# CoreBoard.net
KiCad netlist of a schematic drawn in Altium Designer
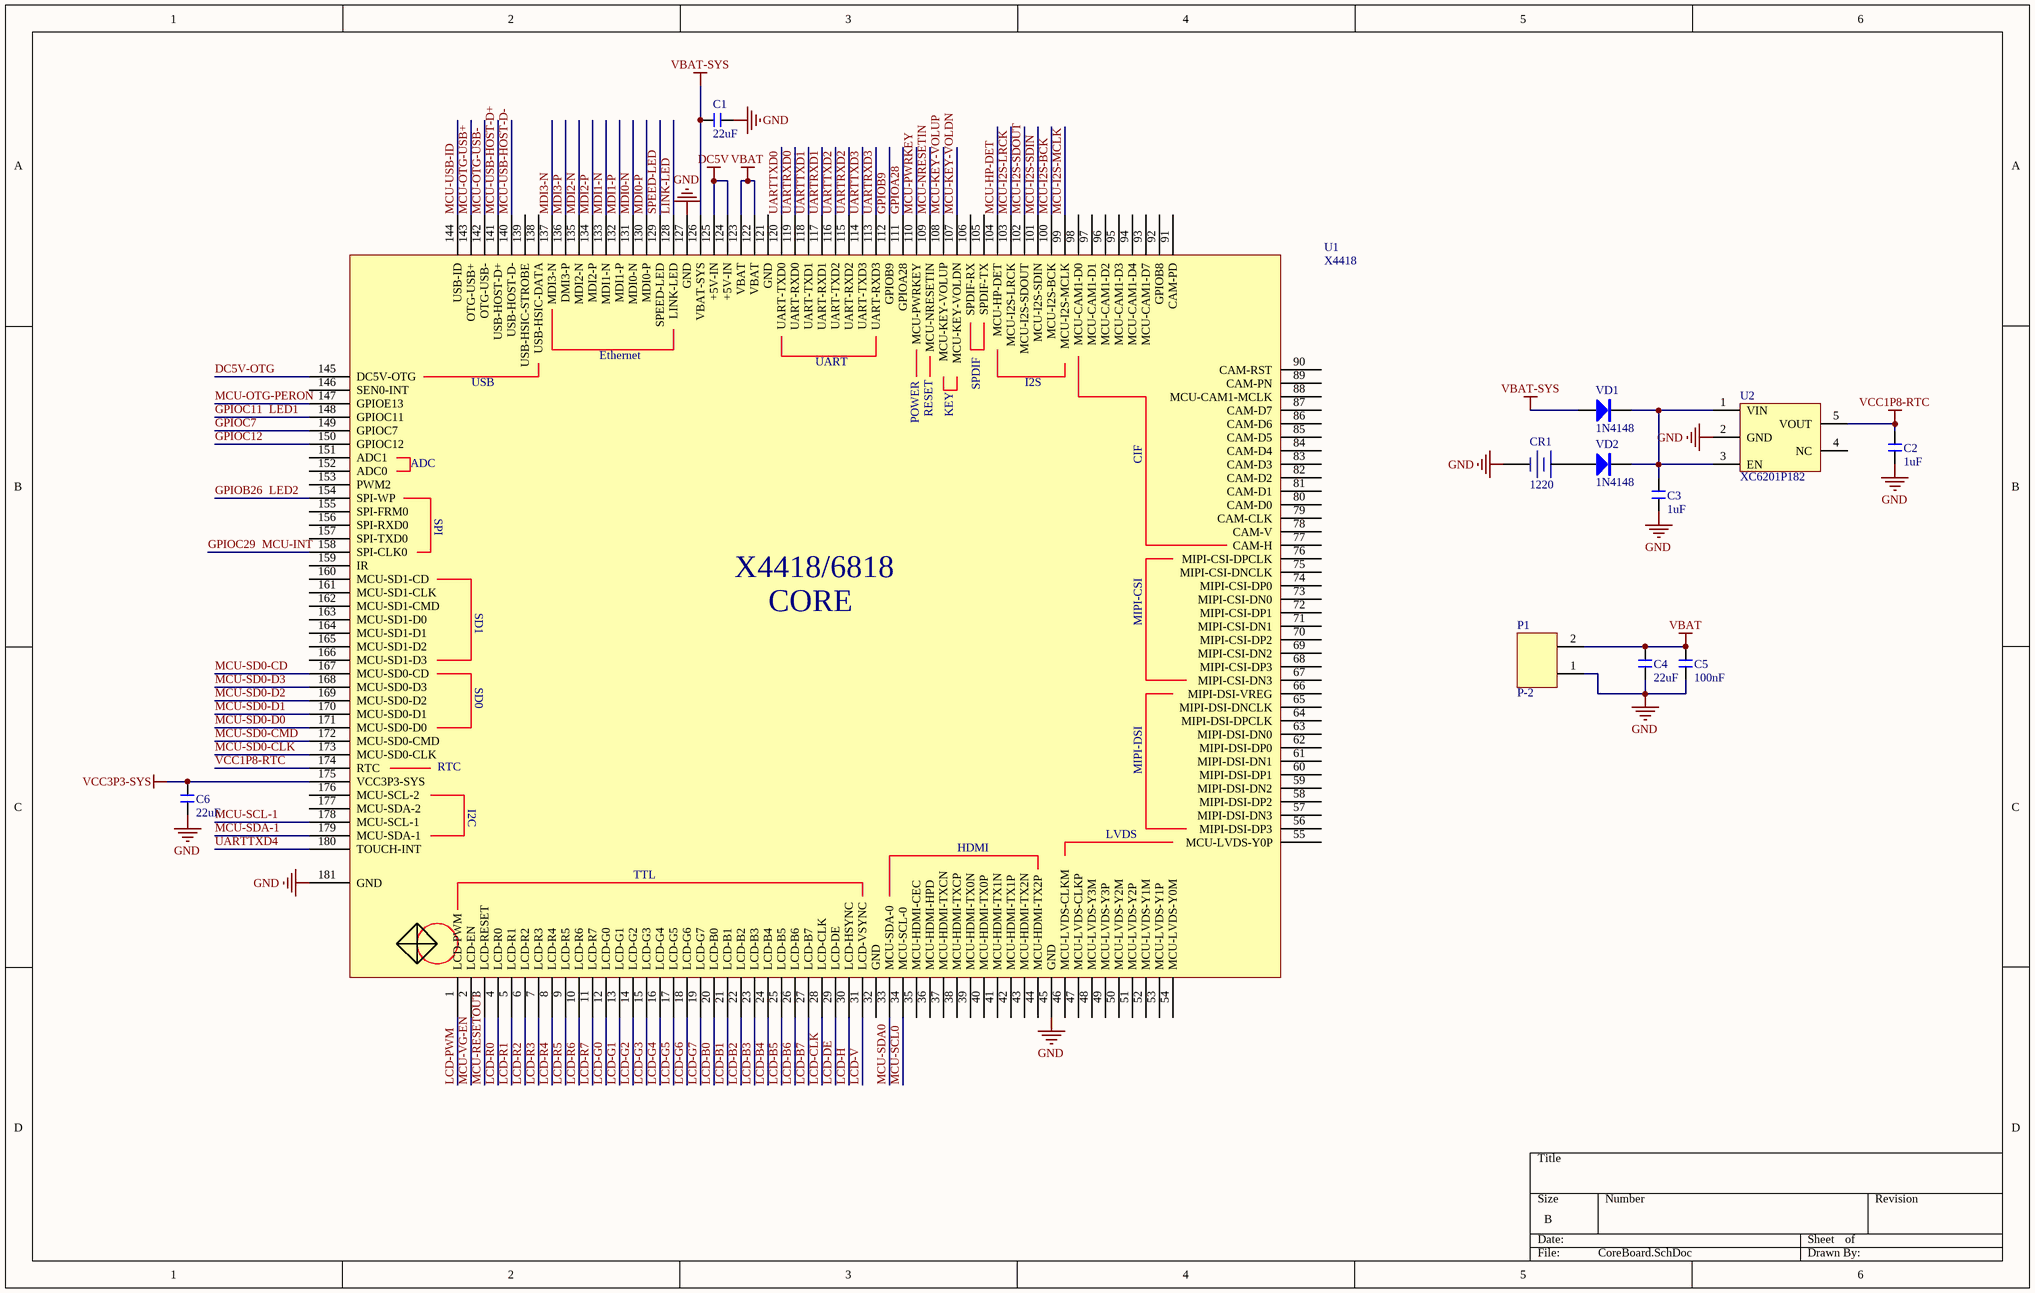
[diagram p0: CoreBoard.SchDoc]

(export (version "E")
  (design (tool "Eeschema 10.0.6"))
  (components
    (comp (ref "C1")
      (value "22uF")
      (footprint "C 0805")
      (description "无极性贴片电容")
      (fields (field (name "版权归属") "源创客"))
      (libsource (lib "ZZF_Library") (part "C 22uF"))
    )
    (comp (ref "C2")
      (value "1uF")
      (footprint "C 0402")
      (description "无极性贴片电容")
      (fields (field (name "版权归属") "源创客"))
      (libsource (lib "ZZF_Library") (part "C 1uF"))
    )
    (comp (ref "C3")
      (value "1uF")
      (footprint "C 0402")
      (description "无极性贴片电容")
      (fields (field (name "版权归属") "源创客"))
      (libsource (lib "ZZF_Library") (part "C 1uF"))
    )
    (comp (ref "C4")
      (value "22uF")
      (footprint "C 0805")
      (description "无极性贴片电容")
      (fields (field (name "版权归属") "源创客"))
      (libsource (lib "ZZF_Library") (part "C 22uF"))
    )
    (comp (ref "C5")
      (value "100nF")
      (footprint "C 0402")
      (description "无极性贴片电容")
      (fields (field (name "版权归属") "源创客"))
      (libsource (lib "ZZF_Library") (part "C 100nF"))
    )
    (comp (ref "C6")
      (value "22uF")
      (footprint "C 0805")
      (description "无极性贴片电容")
      (fields (field (name "版权归属") "源创客"))
      (libsource (lib "ZZF_Library") (part "C 22uF"))
    )
    (comp (ref "CR1")
      (value "1220")
      (footprint "BATTERY CR1220_A")
      (description "微型电池")
      (fields (field (name "版权归属") "源创客"))
      (libsource (lib "ZZF_Library") (part "BATTERY-CR-3V"))
    )
    (comp (ref "P1")
      (value "P-2")
      (footprint "P 2EDG3.5-2H")
      (description "2脚接插件")
      (libsource (lib "ZZF_Library") (part "P-2"))
    )
    (comp (ref "U1")
      (value "X4418")
      (footprint "CORE 4418/6818")
      (description "安卓核心板")
      (libsource (lib "ZZF_Library") (part "CORE X4418/6818"))
    )
    (comp (ref "U2")
      (value "XC6201P182")
      (footprint "SOT23-5M")
      (description "1.8V线性稳压芯片")
      (libsource (lib "ZZF_Library") (part "XC6201P182"))
    )
    (comp (ref "VD1")
      (value "1N4148")
      (footprint "D SOD-323")
      (description "高速开关二极管")
      (fields (field (name "版权归属") "源创客"))
      (libsource (lib "ZZF_Library") (part "1N4148"))
    )
    (comp (ref "VD2")
      (value "1N4148")
      (footprint "D SOD-323")
      (description "高速开关二极管")
      (fields (field (name "版权归属") "源创客"))
      (libsource (lib "ZZF_Library") (part "1N4148"))
    )
  )
  (nets
    (net (code "1") (name "/DC5V-OTG") (class "Default")
      (node (ref "U1") (pin "145") (pinfunction "DC5V-OTG_145") (pintype "passive"))
    )
    (net (code "2") (name "/GPIOA28") (class "Default")
      (node (ref "U1") (pin "111") (pinfunction "GPIOA28_111") (pintype "passive"))
    )
    (net (code "3") (name "/GPIOB9") (class "Default")
      (node (ref "U1") (pin "112") (pinfunction "GPIOB9_112") (pintype "passive"))
    )
    (net (code "4") (name "/GPIOB26") (class "Default")
      (node (ref "U1") (pin "154") (pinfunction "SPI-WP_154") (pintype "passive"))
    )
    (net (code "5") (name "/GPIOC7") (class "Default")
      (node (ref "U1") (pin "149") (pinfunction "GPIOC7_149") (pintype "passive"))
    )
    (net (code "6") (name "/GPIOC11") (class "Default")
      (node (ref "U1") (pin "148") (pinfunction "GPIOC11_148") (pintype "passive"))
    )
    (net (code "7") (name "/GPIOC12") (class "Default")
      (node (ref "U1") (pin "150") (pinfunction "GPIOC12_150") (pintype "passive"))
    )
    (net (code "8") (name "/GPIOC29") (class "Default")
      (node (ref "U1") (pin "158") (pinfunction "SPI-CLK0_158") (pintype "passive"))
    )
    (net (code "9") (name "/LCD-B0") (class "Default")
      (node (ref "U1") (pin "20") (pinfunction "LCD-B0_20") (pintype "passive"))
    )
    (net (code "10") (name "/LCD-B1") (class "Default")
      (node (ref "U1") (pin "21") (pinfunction "LCD-B1_21") (pintype "passive"))
    )
    (net (code "11") (name "/LCD-B2") (class "Default")
      (node (ref "U1") (pin "22") (pinfunction "LCD-B2_22") (pintype "passive"))
    )
    (net (code "12") (name "/LCD-B3") (class "Default")
      (node (ref "U1") (pin "23") (pinfunction "LCD-B3_23") (pintype "passive"))
    )
    (net (code "13") (name "/LCD-B4") (class "Default")
      (node (ref "U1") (pin "24") (pinfunction "LCD-B4_24") (pintype "passive"))
    )
    (net (code "14") (name "/LCD-B5") (class "Default")
      (node (ref "U1") (pin "25") (pinfunction "LCD-B5_25") (pintype "passive"))
    )
    (net (code "15") (name "/LCD-B6") (class "Default")
      (node (ref "U1") (pin "26") (pinfunction "LCD-B6_26") (pintype "passive"))
    )
    (net (code "16") (name "/LCD-B7") (class "Default")
      (node (ref "U1") (pin "27") (pinfunction "LCD-B7_27") (pintype "passive"))
    )
    (net (code "17") (name "/LCD-CLK") (class "Default")
      (node (ref "U1") (pin "28") (pinfunction "LCD-CLK_28") (pintype "passive"))
    )
    (net (code "18") (name "/LCD-DE") (class "Default")
      (node (ref "U1") (pin "29") (pinfunction "LCD-DE_29") (pintype "passive"))
    )
    (net (code "19") (name "/LCD-G0") (class "Default")
      (node (ref "U1") (pin "12") (pinfunction "LCD-G0_12") (pintype "passive"))
    )
    (net (code "20") (name "/LCD-G1") (class "Default")
      (node (ref "U1") (pin "13") (pinfunction "LCD-G1_13") (pintype "passive"))
    )
    (net (code "21") (name "/LCD-G2") (class "Default")
      (node (ref "U1") (pin "14") (pinfunction "LCD-G2_14") (pintype "passive"))
    )
    (net (code "22") (name "/LCD-G3") (class "Default")
      (node (ref "U1") (pin "15") (pinfunction "LCD-G3_15") (pintype "passive"))
    )
    (net (code "23") (name "/LCD-G4") (class "Default")
      (node (ref "U1") (pin "16") (pinfunction "LCD-G4_16") (pintype "passive"))
    )
    (net (code "24") (name "/LCD-G5") (class "Default")
      (node (ref "U1") (pin "17") (pinfunction "LCD-G5_17") (pintype "passive"))
    )
    (net (code "25") (name "/LCD-G6") (class "Default")
      (node (ref "U1") (pin "18") (pinfunction "LCD-G6_18") (pintype "passive"))
    )
    (net (code "26") (name "/LCD-G7") (class "Default")
      (node (ref "U1") (pin "19") (pinfunction "LCD-G7_19") (pintype "passive"))
    )
    (net (code "27") (name "/LCD-H") (class "Default")
      (node (ref "U1") (pin "30") (pinfunction "LCD-HSYNC_30") (pintype "passive"))
    )
    (net (code "28") (name "/LCD-PWM") (class "Default")
      (node (ref "U1") (pin "1") (pinfunction "LCD-PWM_1") (pintype "passive"))
    )
    (net (code "29") (name "/LCD-R0") (class "Default")
      (node (ref "U1") (pin "4") (pinfunction "LCD-R0_4") (pintype "passive"))
    )
    (net (code "30") (name "/LCD-R1") (class "Default")
      (node (ref "U1") (pin "5") (pinfunction "LCD-R1_5") (pintype "passive"))
    )
    (net (code "31") (name "/LCD-R2") (class "Default")
      (node (ref "U1") (pin "6") (pinfunction "LCD-R2_6") (pintype "passive"))
    )
    (net (code "32") (name "/LCD-R3") (class "Default")
      (node (ref "U1") (pin "7") (pinfunction "LCD-R3_7") (pintype "passive"))
    )
    (net (code "33") (name "/LCD-R4") (class "Default")
      (node (ref "U1") (pin "8") (pinfunction "LCD-R4_8") (pintype "passive"))
    )
    (net (code "34") (name "/LCD-R5") (class "Default")
      (node (ref "U1") (pin "9") (pinfunction "LCD-R5_9") (pintype "passive"))
    )
    (net (code "35") (name "/LCD-R6") (class "Default")
      (node (ref "U1") (pin "10") (pinfunction "LCD-R6_10") (pintype "passive"))
    )
    (net (code "36") (name "/LCD-R7") (class "Default")
      (node (ref "U1") (pin "11") (pinfunction "LCD-R7_11") (pintype "passive"))
    )
    (net (code "37") (name "/LCD-V") (class "Default")
      (node (ref "U1") (pin "31") (pinfunction "LCD-VSYNC_31") (pintype "passive"))
    )
    (net (code "38") (name "/LINK-LED") (class "Default")
      (node (ref "U1") (pin "128") (pinfunction "LINK-LED_128") (pintype "passive"))
    )
    (net (code "39") (name "/MCU-HP-DET") (class "Default")
      (node (ref "U1") (pin "104") (pinfunction "MCU-HP-DET_104") (pintype "passive"))
    )
    (net (code "40") (name "/MCU-I2S-BCK") (class "Default")
      (node (ref "U1") (pin "100") (pinfunction "MCU-I2S-BCK_100") (pintype "passive"))
    )
    (net (code "41") (name "/MCU-I2S-LRCK") (class "Default")
      (node (ref "U1") (pin "103") (pinfunction "MCU-I2S-LRCK_103") (pintype "passive"))
    )
    (net (code "42") (name "/MCU-I2S-MCLK") (class "Default")
      (node (ref "U1") (pin "99") (pinfunction "MCU-I2S-MCLK_99") (pintype "passive"))
    )
    (net (code "43") (name "/MCU-I2S-SDIN") (class "Default")
      (node (ref "U1") (pin "101") (pinfunction "MCU-I2S-SDIN_101") (pintype "passive"))
    )
    (net (code "44") (name "/MCU-I2S-SDOUT") (class "Default")
      (node (ref "U1") (pin "102") (pinfunction "MCU-I2S-SDOUT_102") (pintype "passive"))
    )
    (net (code "45") (name "/MCU-KEY-VOLDN") (class "Default")
      (node (ref "U1") (pin "107") (pinfunction "MCU-KEY-VOLDN_107") (pintype "passive"))
    )
    (net (code "46") (name "/MCU-KEY-VOLUP") (class "Default")
      (node (ref "U1") (pin "108") (pinfunction "MCU-KEY-VOLUP_108") (pintype "passive"))
    )
    (net (code "47") (name "/MCU-NRESETIN") (class "Default")
      (node (ref "U1") (pin "109") (pinfunction "MCU-NRESETIN_109") (pintype "passive"))
    )
    (net (code "48") (name "/MCU-OTG-PERON") (class "Default")
      (node (ref "U1") (pin "147") (pinfunction "GPIOE13_147") (pintype "passive"))
    )
    (net (code "49") (name "/MCU-OTG-USB+") (class "Default")
      (node (ref "U1") (pin "143") (pinfunction "OTG-USB+_143") (pintype "passive"))
    )
    (net (code "50") (name "/MCU-OTG-USB-") (class "Default")
      (node (ref "U1") (pin "142") (pinfunction "OTG-USB-_142") (pintype "passive"))
    )
    (net (code "51") (name "/MCU-PWRKEY") (class "Default")
      (node (ref "U1") (pin "110") (pinfunction "MCU-PWRKEY_110") (pintype "passive"))
    )
    (net (code "52") (name "/MCU-RESETOUT") (class "Default")
      (node (ref "U1") (pin "3") (pinfunction "LCD-RESET_3") (pintype "passive"))
    )
    (net (code "53") (name "/MCU-SCL-1") (class "Default")
      (node (ref "U1") (pin "178") (pinfunction "MCU-SCL-1_178") (pintype "passive"))
    )
    (net (code "54") (name "/MCU-SCL0") (class "Default")
      (node (ref "U1") (pin "34") (pinfunction "MCU-SCL-0_34") (pintype "passive"))
    )
    (net (code "55") (name "/MCU-SD0-CD") (class "Default")
      (node (ref "U1") (pin "167") (pinfunction "MCU-SD0-CD_167") (pintype "passive"))
    )
    (net (code "56") (name "/MCU-SD0-CLK") (class "Default")
      (node (ref "U1") (pin "173") (pinfunction "MCU-SD0-CLK_173") (pintype "passive"))
    )
    (net (code "57") (name "/MCU-SD0-CMD") (class "Default")
      (node (ref "U1") (pin "172") (pinfunction "MCU-SD0-CMD_172") (pintype "passive"))
    )
    (net (code "58") (name "/MCU-SD0-D0") (class "Default")
      (node (ref "U1") (pin "171") (pinfunction "MCU-SD0-D0_171") (pintype "passive"))
    )
    (net (code "59") (name "/MCU-SD0-D1") (class "Default")
      (node (ref "U1") (pin "170") (pinfunction "MCU-SD0-D1_170") (pintype "passive"))
    )
    (net (code "60") (name "/MCU-SD0-D2") (class "Default")
      (node (ref "U1") (pin "169") (pinfunction "MCU-SD0-D2_169") (pintype "passive"))
    )
    (net (code "61") (name "/MCU-SD0-D3") (class "Default")
      (node (ref "U1") (pin "168") (pinfunction "MCU-SD0-D3_168") (pintype "passive"))
    )
    (net (code "62") (name "/MCU-SDA-1") (class "Default")
      (node (ref "U1") (pin "179") (pinfunction "MCU-SDA-1_179") (pintype "passive"))
    )
    (net (code "63") (name "/MCU-SDA0") (class "Default")
      (node (ref "U1") (pin "33") (pinfunction "MCU-SDA-0_33") (pintype "passive"))
    )
    (net (code "64") (name "/MCU-USB-HOST-D+") (class "Default")
      (node (ref "U1") (pin "141") (pinfunction "USB-HOST-D+_141") (pintype "passive"))
    )
    (net (code "65") (name "/MCU-USB-HOST-D-") (class "Default")
      (node (ref "U1") (pin "140") (pinfunction "USB-HOST-D-_140") (pintype "passive"))
    )
    (net (code "66") (name "/MCU-USB-ID") (class "Default")
      (node (ref "U1") (pin "144") (pinfunction "USB-ID_144") (pintype "passive"))
    )
    (net (code "67") (name "/MCU-VG-EN") (class "Default")
      (node (ref "U1") (pin "2") (pinfunction "LCD-EN_2") (pintype "passive"))
    )
    (net (code "68") (name "/MDI0-N") (class "Default")
      (node (ref "U1") (pin "131") (pinfunction "MDI0-N_131") (pintype "passive"))
    )
    (net (code "69") (name "/MDI0-P") (class "Default")
      (node (ref "U1") (pin "130") (pinfunction "MDI0-P_130") (pintype "passive"))
    )
    (net (code "70") (name "/MDI1-N") (class "Default")
      (node (ref "U1") (pin "133") (pinfunction "MDI1-N_133") (pintype "passive"))
    )
    (net (code "71") (name "/MDI1-P") (class "Default")
      (node (ref "U1") (pin "132") (pinfunction "MDI1-P_132") (pintype "passive"))
    )
    (net (code "72") (name "/MDI2-N") (class "Default")
      (node (ref "U1") (pin "135") (pinfunction "MDI2-N_135") (pintype "passive"))
    )
    (net (code "73") (name "/MDI2-P") (class "Default")
      (node (ref "U1") (pin "134") (pinfunction "MDI2-P_134") (pintype "passive"))
    )
    (net (code "74") (name "/MDI3-N") (class "Default")
      (node (ref "U1") (pin "137") (pinfunction "MDI3-N_137") (pintype "passive"))
    )
    (net (code "75") (name "/MDI3-P") (class "Default")
      (node (ref "U1") (pin "136") (pinfunction "DMI3-P_136") (pintype "passive"))
    )
    (net (code "76") (name "/SPEED-LED") (class "Default")
      (node (ref "U1") (pin "129") (pinfunction "SPEED-LED_129") (pintype "passive"))
    )
    (net (code "77") (name "/UARTRXD0") (class "Default")
      (node (ref "U1") (pin "119") (pinfunction "UART-RXD0_119") (pintype "passive"))
    )
    (net (code "78") (name "/UARTRXD1") (class "Default")
      (node (ref "U1") (pin "117") (pinfunction "UART-RXD1_117") (pintype "passive"))
    )
    (net (code "79") (name "/UARTRXD2") (class "Default")
      (node (ref "U1") (pin "115") (pinfunction "UART-RXD2_115") (pintype "passive"))
    )
    (net (code "80") (name "/UARTRXD3") (class "Default")
      (node (ref "U1") (pin "113") (pinfunction "UART-RXD3_113") (pintype "passive"))
    )
    (net (code "81") (name "/UARTTXD0") (class "Default")
      (node (ref "U1") (pin "120") (pinfunction "UART-TXD0_120") (pintype "passive"))
    )
    (net (code "82") (name "/UARTTXD1") (class "Default")
      (node (ref "U1") (pin "118") (pinfunction "UART-TXD1_118") (pintype "passive"))
    )
    (net (code "83") (name "/UARTTXD2") (class "Default")
      (node (ref "U1") (pin "116") (pinfunction "UART-TXD2_116") (pintype "passive"))
    )
    (net (code "84") (name "/UARTTXD3") (class "Default")
      (node (ref "U1") (pin "114") (pinfunction "UART-TXD3_114") (pintype "passive"))
    )
    (net (code "85") (name "/UARTTXD4") (class "Default")
      (node (ref "U1") (pin "180") (pinfunction "TOUCH-INT_180") (pintype "passive"))
    )
    (net (code "86") (name "DC5V") (class "Default")
      (node (ref "U1") (pin "124") (pinfunction "+5V-IN_124") (pintype "passive"))
      (node (ref "U1") (pin "125") (pinfunction "+5V-IN_125") (pintype "passive"))
    )
    (net (code "87") (name "GND") (class "Default")
      (node (ref "C1") (pin "2") (pinfunction "2_2") (pintype "passive"))
      (node (ref "C2") (pin "1") (pinfunction "1_1") (pintype "passive"))
      (node (ref "C3") (pin "1") (pinfunction "1_1") (pintype "passive"))
      (node (ref "C4") (pin "1") (pinfunction "1_1") (pintype "passive"))
      (node (ref "C5") (pin "1") (pinfunction "1_1") (pintype "passive"))
      (node (ref "C6") (pin "1") (pinfunction "1_1") (pintype "passive"))
      (node (ref "CR1") (pin "DC-") (pinfunction "DC-_DC-") (pintype "passive"))
      (node (ref "P1") (pin "1") (pinfunction "1_1") (pintype "passive"))
      (node (ref "U1") (pin "127") (pinfunction "GND_127") (pintype "passive"))
      (node (ref "U1") (pin "181") (pinfunction "GND_181") (pintype "passive"))
      (node (ref "U1") (pin "45") (pinfunction "GND_45") (pintype "passive"))
      (node (ref "U2") (pin "2") (pinfunction "GND_2") (pintype "passive"))
    )
    (net (code "88") (name "Net-(CR1-PadDC+)") (class "Default")
      (node (ref "CR1") (pin "DC+") (pinfunction "DC+_DC+") (pintype "passive"))
      (node (ref "VD2") (pin "A") (pinfunction "A_A") (pintype "passive"))
    )
    (net (code "89") (name "Net-(U2-EN)") (class "Default")
      (node (ref "C3") (pin "2") (pinfunction "2_2") (pintype "passive"))
      (node (ref "U2") (pin "1") (pinfunction "VIN_1") (pintype "passive"))
      (node (ref "U2") (pin "3") (pinfunction "EN_3") (pintype "passive"))
      (node (ref "VD1") (pin "K") (pinfunction "K_K") (pintype "passive"))
      (node (ref "VD2") (pin "K") (pinfunction "K_K") (pintype "passive"))
    )
    (net (code "90") (name "VBAT") (class "Default")
      (node (ref "C4") (pin "2") (pinfunction "2_2") (pintype "passive"))
      (node (ref "C5") (pin "2") (pinfunction "2_2") (pintype "passive"))
      (node (ref "P1") (pin "2") (pinfunction "2_2") (pintype "passive"))
      (node (ref "U1") (pin "122") (pinfunction "VBAT_122") (pintype "passive"))
      (node (ref "U1") (pin "123") (pinfunction "VBAT_123") (pintype "passive"))
    )
    (net (code "91") (name "VBAT-SYS") (class "Default")
      (node (ref "C1") (pin "1") (pinfunction "1_1") (pintype "passive"))
      (node (ref "U1") (pin "126") (pinfunction "VBAT-SYS_126") (pintype "passive"))
      (node (ref "VD1") (pin "A") (pinfunction "A_A") (pintype "passive"))
    )
    (net (code "92") (name "VCC1P8-RTC") (class "Default")
      (node (ref "C2") (pin "2") (pinfunction "2_2") (pintype "passive"))
      (node (ref "U1") (pin "174") (pinfunction "RTC_174") (pintype "passive"))
      (node (ref "U2") (pin "5") (pinfunction "VOUT_5") (pintype "passive"))
    )
    (net (code "93") (name "VCC3P3-SYS") (class "Default")
      (node (ref "C6") (pin "2") (pinfunction "2_2") (pintype "passive"))
      (node (ref "U1") (pin "175") (pinfunction "VCC3P3-SYS_175") (pintype "passive"))
    )
    (net (code "94") (name "unconnected-(U1-ADC0-Pad152)") (class "Default")
      (node (ref "U1") (pin "152") (pinfunction "ADC0_152") (pintype "passive"))
    )
    (net (code "95") (name "unconnected-(U1-ADC1-Pad151)") (class "Default")
      (node (ref "U1") (pin "151") (pinfunction "ADC1_151") (pintype "passive"))
    )
    (net (code "96") (name "unconnected-(U1-CAM-CLK-Pad79)") (class "Default")
      (node (ref "U1") (pin "79") (pinfunction "CAM-CLK_79") (pintype "passive"))
    )
    (net (code "97") (name "unconnected-(U1-CAM-D0-Pad80)") (class "Default")
      (node (ref "U1") (pin "80") (pinfunction "CAM-D0_80") (pintype "passive"))
    )
    (net (code "98") (name "unconnected-(U1-CAM-D1-Pad81)") (class "Default")
      (node (ref "U1") (pin "81") (pinfunction "CAM-D1_81") (pintype "passive"))
    )
    (net (code "99") (name "unconnected-(U1-CAM-D2-Pad82)") (class "Default")
      (node (ref "U1") (pin "82") (pinfunction "CAM-D2_82") (pintype "passive"))
    )
    (net (code "100") (name "unconnected-(U1-CAM-D3-Pad83)") (class "Default")
      (node (ref "U1") (pin "83") (pinfunction "CAM-D3_83") (pintype "passive"))
    )
    (net (code "101") (name "unconnected-(U1-CAM-D4-Pad84)") (class "Default")
      (node (ref "U1") (pin "84") (pinfunction "CAM-D4_84") (pintype "passive"))
    )
    (net (code "102") (name "unconnected-(U1-CAM-D5-Pad85)") (class "Default")
      (node (ref "U1") (pin "85") (pinfunction "CAM-D5_85") (pintype "passive"))
    )
    (net (code "103") (name "unconnected-(U1-CAM-D6-Pad86)") (class "Default")
      (node (ref "U1") (pin "86") (pinfunction "CAM-D6_86") (pintype "passive"))
    )
    (net (code "104") (name "unconnected-(U1-CAM-D7-Pad87)") (class "Default")
      (node (ref "U1") (pin "87") (pinfunction "CAM-D7_87") (pintype "passive"))
    )
    (net (code "105") (name "unconnected-(U1-CAM-H-Pad77)") (class "Default")
      (node (ref "U1") (pin "77") (pinfunction "CAM-H_77") (pintype "passive"))
    )
    (net (code "106") (name "unconnected-(U1-CAM-PD-Pad91)") (class "Default")
      (node (ref "U1") (pin "91") (pinfunction "CAM-PD_91") (pintype "passive"))
    )
    (net (code "107") (name "unconnected-(U1-CAM-PN-Pad89)") (class "Default")
      (node (ref "U1") (pin "89") (pinfunction "CAM-PN_89") (pintype "passive"))
    )
    (net (code "108") (name "unconnected-(U1-CAM-RST-Pad90)") (class "Default")
      (node (ref "U1") (pin "90") (pinfunction "CAM-RST_90") (pintype "passive"))
    )
    (net (code "109") (name "unconnected-(U1-CAM-V-Pad78)") (class "Default")
      (node (ref "U1") (pin "78") (pinfunction "CAM-V_78") (pintype "passive"))
    )
    (net (code "110") (name "unconnected-(U1-GND-Pad32)") (class "Default")
      (node (ref "U1") (pin "32") (pinfunction "GND_32") (pintype "passive"))
    )
    (net (code "111") (name "unconnected-(U1-GND-Pad121)") (class "Default")
      (node (ref "U1") (pin "121") (pinfunction "GND_121") (pintype "passive"))
    )
    (net (code "112") (name "unconnected-(U1-GPIOB8-Pad92)") (class "Default")
      (node (ref "U1") (pin "92") (pinfunction "GPIOB8_92") (pintype "passive"))
    )
    (net (code "113") (name "unconnected-(U1-IR-Pad159)") (class "Default")
      (node (ref "U1") (pin "159") (pinfunction "IR_159") (pintype "passive"))
    )
    (net (code "114") (name "unconnected-(U1-MCU-CAM1-D0-Pad98)") (class "Default")
      (node (ref "U1") (pin "98") (pinfunction "MCU-CAM1-D0_98") (pintype "passive"))
    )
    (net (code "115") (name "unconnected-(U1-MCU-CAM1-D1-Pad97)") (class "Default")
      (node (ref "U1") (pin "97") (pinfunction "MCU-CAM1-D1_97") (pintype "passive"))
    )
    (net (code "116") (name "unconnected-(U1-MCU-CAM1-D2-Pad96)") (class "Default")
      (node (ref "U1") (pin "96") (pinfunction "MCU-CAM1-D2_96") (pintype "passive"))
    )
    (net (code "117") (name "unconnected-(U1-MCU-CAM1-D3-Pad95)") (class "Default")
      (node (ref "U1") (pin "95") (pinfunction "MCU-CAM1-D3_95") (pintype "passive"))
    )
    (net (code "118") (name "unconnected-(U1-MCU-CAM1-D4-Pad94)") (class "Default")
      (node (ref "U1") (pin "94") (pinfunction "MCU-CAM1-D4_94") (pintype "passive"))
    )
    (net (code "119") (name "unconnected-(U1-MCU-CAM1-D7-Pad93)") (class "Default")
      (node (ref "U1") (pin "93") (pinfunction "MCU-CAM1-D7_93") (pintype "passive"))
    )
    (net (code "120") (name "unconnected-(U1-MCU-CAM1-MCLK-Pad88)") (class "Default")
      (node (ref "U1") (pin "88") (pinfunction "MCU-CAM1-MCLK_88") (pintype "passive"))
    )
    (net (code "121") (name "unconnected-(U1-MCU-HDMI-CEC-Pad35)") (class "Default")
      (node (ref "U1") (pin "35") (pinfunction "MCU-HDMI-CEC_35") (pintype "passive"))
    )
    (net (code "122") (name "unconnected-(U1-MCU-HDMI-HPD-Pad36)") (class "Default")
      (node (ref "U1") (pin "36") (pinfunction "MCU-HDMI-HPD_36") (pintype "passive"))
    )
    (net (code "123") (name "unconnected-(U1-MCU-HDMI-TX0N-Pad39)") (class "Default")
      (node (ref "U1") (pin "39") (pinfunction "MCU-HDMI-TX0N_39") (pintype "passive"))
    )
    (net (code "124") (name "unconnected-(U1-MCU-HDMI-TX0P-Pad40)") (class "Default")
      (node (ref "U1") (pin "40") (pinfunction "MCU-HDMI-TX0P_40") (pintype "passive"))
    )
    (net (code "125") (name "unconnected-(U1-MCU-HDMI-TX1N-Pad41)") (class "Default")
      (node (ref "U1") (pin "41") (pinfunction "MCU-HDMI-TX1N_41") (pintype "passive"))
    )
    (net (code "126") (name "unconnected-(U1-MCU-HDMI-TX1P-Pad42)") (class "Default")
      (node (ref "U1") (pin "42") (pinfunction "MCU-HDMI-TX1P_42") (pintype "passive"))
    )
    (net (code "127") (name "unconnected-(U1-MCU-HDMI-TX2N-Pad43)") (class "Default")
      (node (ref "U1") (pin "43") (pinfunction "MCU-HDMI-TX2N_43") (pintype "passive"))
    )
    (net (code "128") (name "unconnected-(U1-MCU-HDMI-TX2P-Pad44)") (class "Default")
      (node (ref "U1") (pin "44") (pinfunction "MCU-HDMI-TX2P_44") (pintype "passive"))
    )
    (net (code "129") (name "unconnected-(U1-MCU-HDMI-TXCN-Pad37)") (class "Default")
      (node (ref "U1") (pin "37") (pinfunction "MCU-HDMI-TXCN_37") (pintype "passive"))
    )
    (net (code "130") (name "unconnected-(U1-MCU-HDMI-TXCP-Pad38)") (class "Default")
      (node (ref "U1") (pin "38") (pinfunction "MCU-HDMI-TXCP_38") (pintype "passive"))
    )
    (net (code "131") (name "unconnected-(U1-MCU-LVDS-CLKM-Pad46)") (class "Default")
      (node (ref "U1") (pin "46") (pinfunction "MCU-LVDS-CLKM_46") (pintype "passive"))
    )
    (net (code "132") (name "unconnected-(U1-MCU-LVDS-CLKP-Pad47)") (class "Default")
      (node (ref "U1") (pin "47") (pinfunction "MCU-LVDS-CLKP_47") (pintype "passive"))
    )
    (net (code "133") (name "unconnected-(U1-MCU-LVDS-Y0M-Pad54)") (class "Default")
      (node (ref "U1") (pin "54") (pinfunction "MCU-LVDS-Y0M_54") (pintype "passive"))
    )
    (net (code "134") (name "unconnected-(U1-MCU-LVDS-Y0P-Pad55)") (class "Default")
      (node (ref "U1") (pin "55") (pinfunction "MCU-LVDS-Y0P_55") (pintype "passive"))
    )
    (net (code "135") (name "unconnected-(U1-MCU-LVDS-Y1M-Pad52)") (class "Default")
      (node (ref "U1") (pin "52") (pinfunction "MCU-LVDS-Y1M_52") (pintype "passive"))
    )
    (net (code "136") (name "unconnected-(U1-MCU-LVDS-Y1P-Pad53)") (class "Default")
      (node (ref "U1") (pin "53") (pinfunction "MCU-LVDS-Y1P_53") (pintype "passive"))
    )
    (net (code "137") (name "unconnected-(U1-MCU-LVDS-Y2M-Pad50)") (class "Default")
      (node (ref "U1") (pin "50") (pinfunction "MCU-LVDS-Y2M_50") (pintype "passive"))
    )
    (net (code "138") (name "unconnected-(U1-MCU-LVDS-Y2P-Pad51)") (class "Default")
      (node (ref "U1") (pin "51") (pinfunction "MCU-LVDS-Y2P_51") (pintype "passive"))
    )
    (net (code "139") (name "unconnected-(U1-MCU-LVDS-Y3M-Pad48)") (class "Default")
      (node (ref "U1") (pin "48") (pinfunction "MCU-LVDS-Y3M_48") (pintype "passive"))
    )
    (net (code "140") (name "unconnected-(U1-MCU-LVDS-Y3P-Pad49)") (class "Default")
      (node (ref "U1") (pin "49") (pinfunction "MCU-LVDS-Y3P_49") (pintype "passive"))
    )
    (net (code "141") (name "unconnected-(U1-MCU-SCL-2-Pad176)") (class "Default")
      (node (ref "U1") (pin "176") (pinfunction "MCU-SCL-2_176") (pintype "passive"))
    )
    (net (code "142") (name "unconnected-(U1-MCU-SD1-CD-Pad160)") (class "Default")
      (node (ref "U1") (pin "160") (pinfunction "MCU-SD1-CD_160") (pintype "passive"))
    )
    (net (code "143") (name "unconnected-(U1-MCU-SD1-CLK-Pad161)") (class "Default")
      (node (ref "U1") (pin "161") (pinfunction "MCU-SD1-CLK_161") (pintype "passive"))
    )
    (net (code "144") (name "unconnected-(U1-MCU-SD1-CMD-Pad162)") (class "Default")
      (node (ref "U1") (pin "162") (pinfunction "MCU-SD1-CMD_162") (pintype "passive"))
    )
    (net (code "145") (name "unconnected-(U1-MCU-SD1-D0-Pad163)") (class "Default")
      (node (ref "U1") (pin "163") (pinfunction "MCU-SD1-D0_163") (pintype "passive"))
    )
    (net (code "146") (name "unconnected-(U1-MCU-SD1-D1-Pad164)") (class "Default")
      (node (ref "U1") (pin "164") (pinfunction "MCU-SD1-D1_164") (pintype "passive"))
    )
    (net (code "147") (name "unconnected-(U1-MCU-SD1-D2-Pad165)") (class "Default")
      (node (ref "U1") (pin "165") (pinfunction "MCU-SD1-D2_165") (pintype "passive"))
    )
    (net (code "148") (name "unconnected-(U1-MCU-SD1-D3-Pad166)") (class "Default")
      (node (ref "U1") (pin "166") (pinfunction "MCU-SD1-D3_166") (pintype "passive"))
    )
    (net (code "149") (name "unconnected-(U1-MCU-SDA-2-Pad177)") (class "Default")
      (node (ref "U1") (pin "177") (pinfunction "MCU-SDA-2_177") (pintype "passive"))
    )
    (net (code "150") (name "unconnected-(U1-MIPI-CSI-DN0-Pad73)") (class "Default")
      (node (ref "U1") (pin "73") (pinfunction "MIPI-CSI-DN0_73") (pintype "passive"))
    )
    (net (code "151") (name "unconnected-(U1-MIPI-CSI-DN1-Pad71)") (class "Default")
      (node (ref "U1") (pin "71") (pinfunction "MIPI-CSI-DN1_71") (pintype "passive"))
    )
    (net (code "152") (name "unconnected-(U1-MIPI-CSI-DN2-Pad69)") (class "Default")
      (node (ref "U1") (pin "69") (pinfunction "MIPI-CSI-DN2_69") (pintype "passive"))
    )
    (net (code "153") (name "unconnected-(U1-MIPI-CSI-DN3-Pad67)") (class "Default")
      (node (ref "U1") (pin "67") (pinfunction "MIPI-CSI-DN3_67") (pintype "passive"))
    )
    (net (code "154") (name "unconnected-(U1-MIPI-CSI-DNCLK-Pad75)") (class "Default")
      (node (ref "U1") (pin "75") (pinfunction "MIPI-CSI-DNCLK_75") (pintype "passive"))
    )
    (net (code "155") (name "unconnected-(U1-MIPI-CSI-DP0-Pad74)") (class "Default")
      (node (ref "U1") (pin "74") (pinfunction "MIPI-CSI-DP0_74") (pintype "passive"))
    )
    (net (code "156") (name "unconnected-(U1-MIPI-CSI-DP1-Pad72)") (class "Default")
      (node (ref "U1") (pin "72") (pinfunction "MIPI-CSI-DP1_72") (pintype "passive"))
    )
    (net (code "157") (name "unconnected-(U1-MIPI-CSI-DP2-Pad70)") (class "Default")
      (node (ref "U1") (pin "70") (pinfunction "MIPI-CSI-DP2_70") (pintype "passive"))
    )
    (net (code "158") (name "unconnected-(U1-MIPI-CSI-DP3-Pad68)") (class "Default")
      (node (ref "U1") (pin "68") (pinfunction "MIPI-CSI-DP3_68") (pintype "passive"))
    )
    (net (code "159") (name "unconnected-(U1-MIPI-CSI-DPCLK-Pad76)") (class "Default")
      (node (ref "U1") (pin "76") (pinfunction "MIPI-CSI-DPCLK_76") (pintype "passive"))
    )
    (net (code "160") (name "unconnected-(U1-MIPI-DSI-DN0-Pad63)") (class "Default")
      (node (ref "U1") (pin "63") (pinfunction "MIPI-DSI-DN0_63") (pintype "passive"))
    )
    (net (code "161") (name "unconnected-(U1-MIPI-DSI-DN1-Pad61)") (class "Default")
      (node (ref "U1") (pin "61") (pinfunction "MIPI-DSI-DN1_61") (pintype "passive"))
    )
    (net (code "162") (name "unconnected-(U1-MIPI-DSI-DN2-Pad59)") (class "Default")
      (node (ref "U1") (pin "59") (pinfunction "MIPI-DSI-DN2_59") (pintype "passive"))
    )
    (net (code "163") (name "unconnected-(U1-MIPI-DSI-DN3-Pad57)") (class "Default")
      (node (ref "U1") (pin "57") (pinfunction "MIPI-DSI-DN3_57") (pintype "passive"))
    )
    (net (code "164") (name "unconnected-(U1-MIPI-DSI-DNCLK-Pad65)") (class "Default")
      (node (ref "U1") (pin "65") (pinfunction "MIPI-DSI-DNCLK_65") (pintype "passive"))
    )
    (net (code "165") (name "unconnected-(U1-MIPI-DSI-DP0-Pad62)") (class "Default")
      (node (ref "U1") (pin "62") (pinfunction "MIPI-DSI-DP0_62") (pintype "passive"))
    )
    (net (code "166") (name "unconnected-(U1-MIPI-DSI-DP1-Pad60)") (class "Default")
      (node (ref "U1") (pin "60") (pinfunction "MIPI-DSI-DP1_60") (pintype "passive"))
    )
    (net (code "167") (name "unconnected-(U1-MIPI-DSI-DP2-Pad58)") (class "Default")
      (node (ref "U1") (pin "58") (pinfunction "MIPI-DSI-DP2_58") (pintype "passive"))
    )
    (net (code "168") (name "unconnected-(U1-MIPI-DSI-DP3-Pad56)") (class "Default")
      (node (ref "U1") (pin "56") (pinfunction "MIPI-DSI-DP3_56") (pintype "passive"))
    )
    (net (code "169") (name "unconnected-(U1-MIPI-DSI-DPCLK-Pad64)") (class "Default")
      (node (ref "U1") (pin "64") (pinfunction "MIPI-DSI-DPCLK_64") (pintype "passive"))
    )
    (net (code "170") (name "unconnected-(U1-MIPI-DSI-VREG-Pad66)") (class "Default")
      (node (ref "U1") (pin "66") (pinfunction "MIPI-DSI-VREG_66") (pintype "passive"))
    )
    (net (code "171") (name "unconnected-(U1-PWM2-Pad153)") (class "Default")
      (node (ref "U1") (pin "153") (pinfunction "PWM2_153") (pintype "passive"))
    )
    (net (code "172") (name "unconnected-(U1-SEN0-INT-Pad146)") (class "Default")
      (node (ref "U1") (pin "146") (pinfunction "SEN0-INT_146") (pintype "passive"))
    )
    (net (code "173") (name "unconnected-(U1-SPDIF-RX-Pad106)") (class "Default")
      (node (ref "U1") (pin "106") (pinfunction "SPDIF-RX_106") (pintype "passive"))
    )
    (net (code "174") (name "unconnected-(U1-SPDIF-TX-Pad105)") (class "Default")
      (node (ref "U1") (pin "105") (pinfunction "SPDIF-TX_105") (pintype "passive"))
    )
    (net (code "175") (name "unconnected-(U1-SPI-FRM0-Pad155)") (class "Default")
      (node (ref "U1") (pin "155") (pinfunction "SPI-FRM0_155") (pintype "passive"))
    )
    (net (code "176") (name "unconnected-(U1-SPI-RXD0-Pad156)") (class "Default")
      (node (ref "U1") (pin "156") (pinfunction "SPI-RXD0_156") (pintype "passive"))
    )
    (net (code "177") (name "unconnected-(U1-SPI-TXD0-Pad157)") (class "Default")
      (node (ref "U1") (pin "157") (pinfunction "SPI-TXD0_157") (pintype "passive"))
    )
    (net (code "178") (name "unconnected-(U1-USB-HSIC-DATA-Pad138)") (class "Default")
      (node (ref "U1") (pin "138") (pinfunction "USB-HSIC-DATA_138") (pintype "passive"))
    )
    (net (code "179") (name "unconnected-(U1-USB-HSIC-STROBE-Pad139)") (class "Default")
      (node (ref "U1") (pin "139") (pinfunction "USB-HSIC-STROBE_139") (pintype "passive"))
    )
    (net (code "180") (name "unconnected-(U2-NC-Pad4)") (class "Default")
      (node (ref "U2") (pin "4") (pinfunction "NC_4") (pintype "passive"))
    )
  )
)
